# MB_Power.net
KiCad netlist of a schematic drawn in Altium Designer
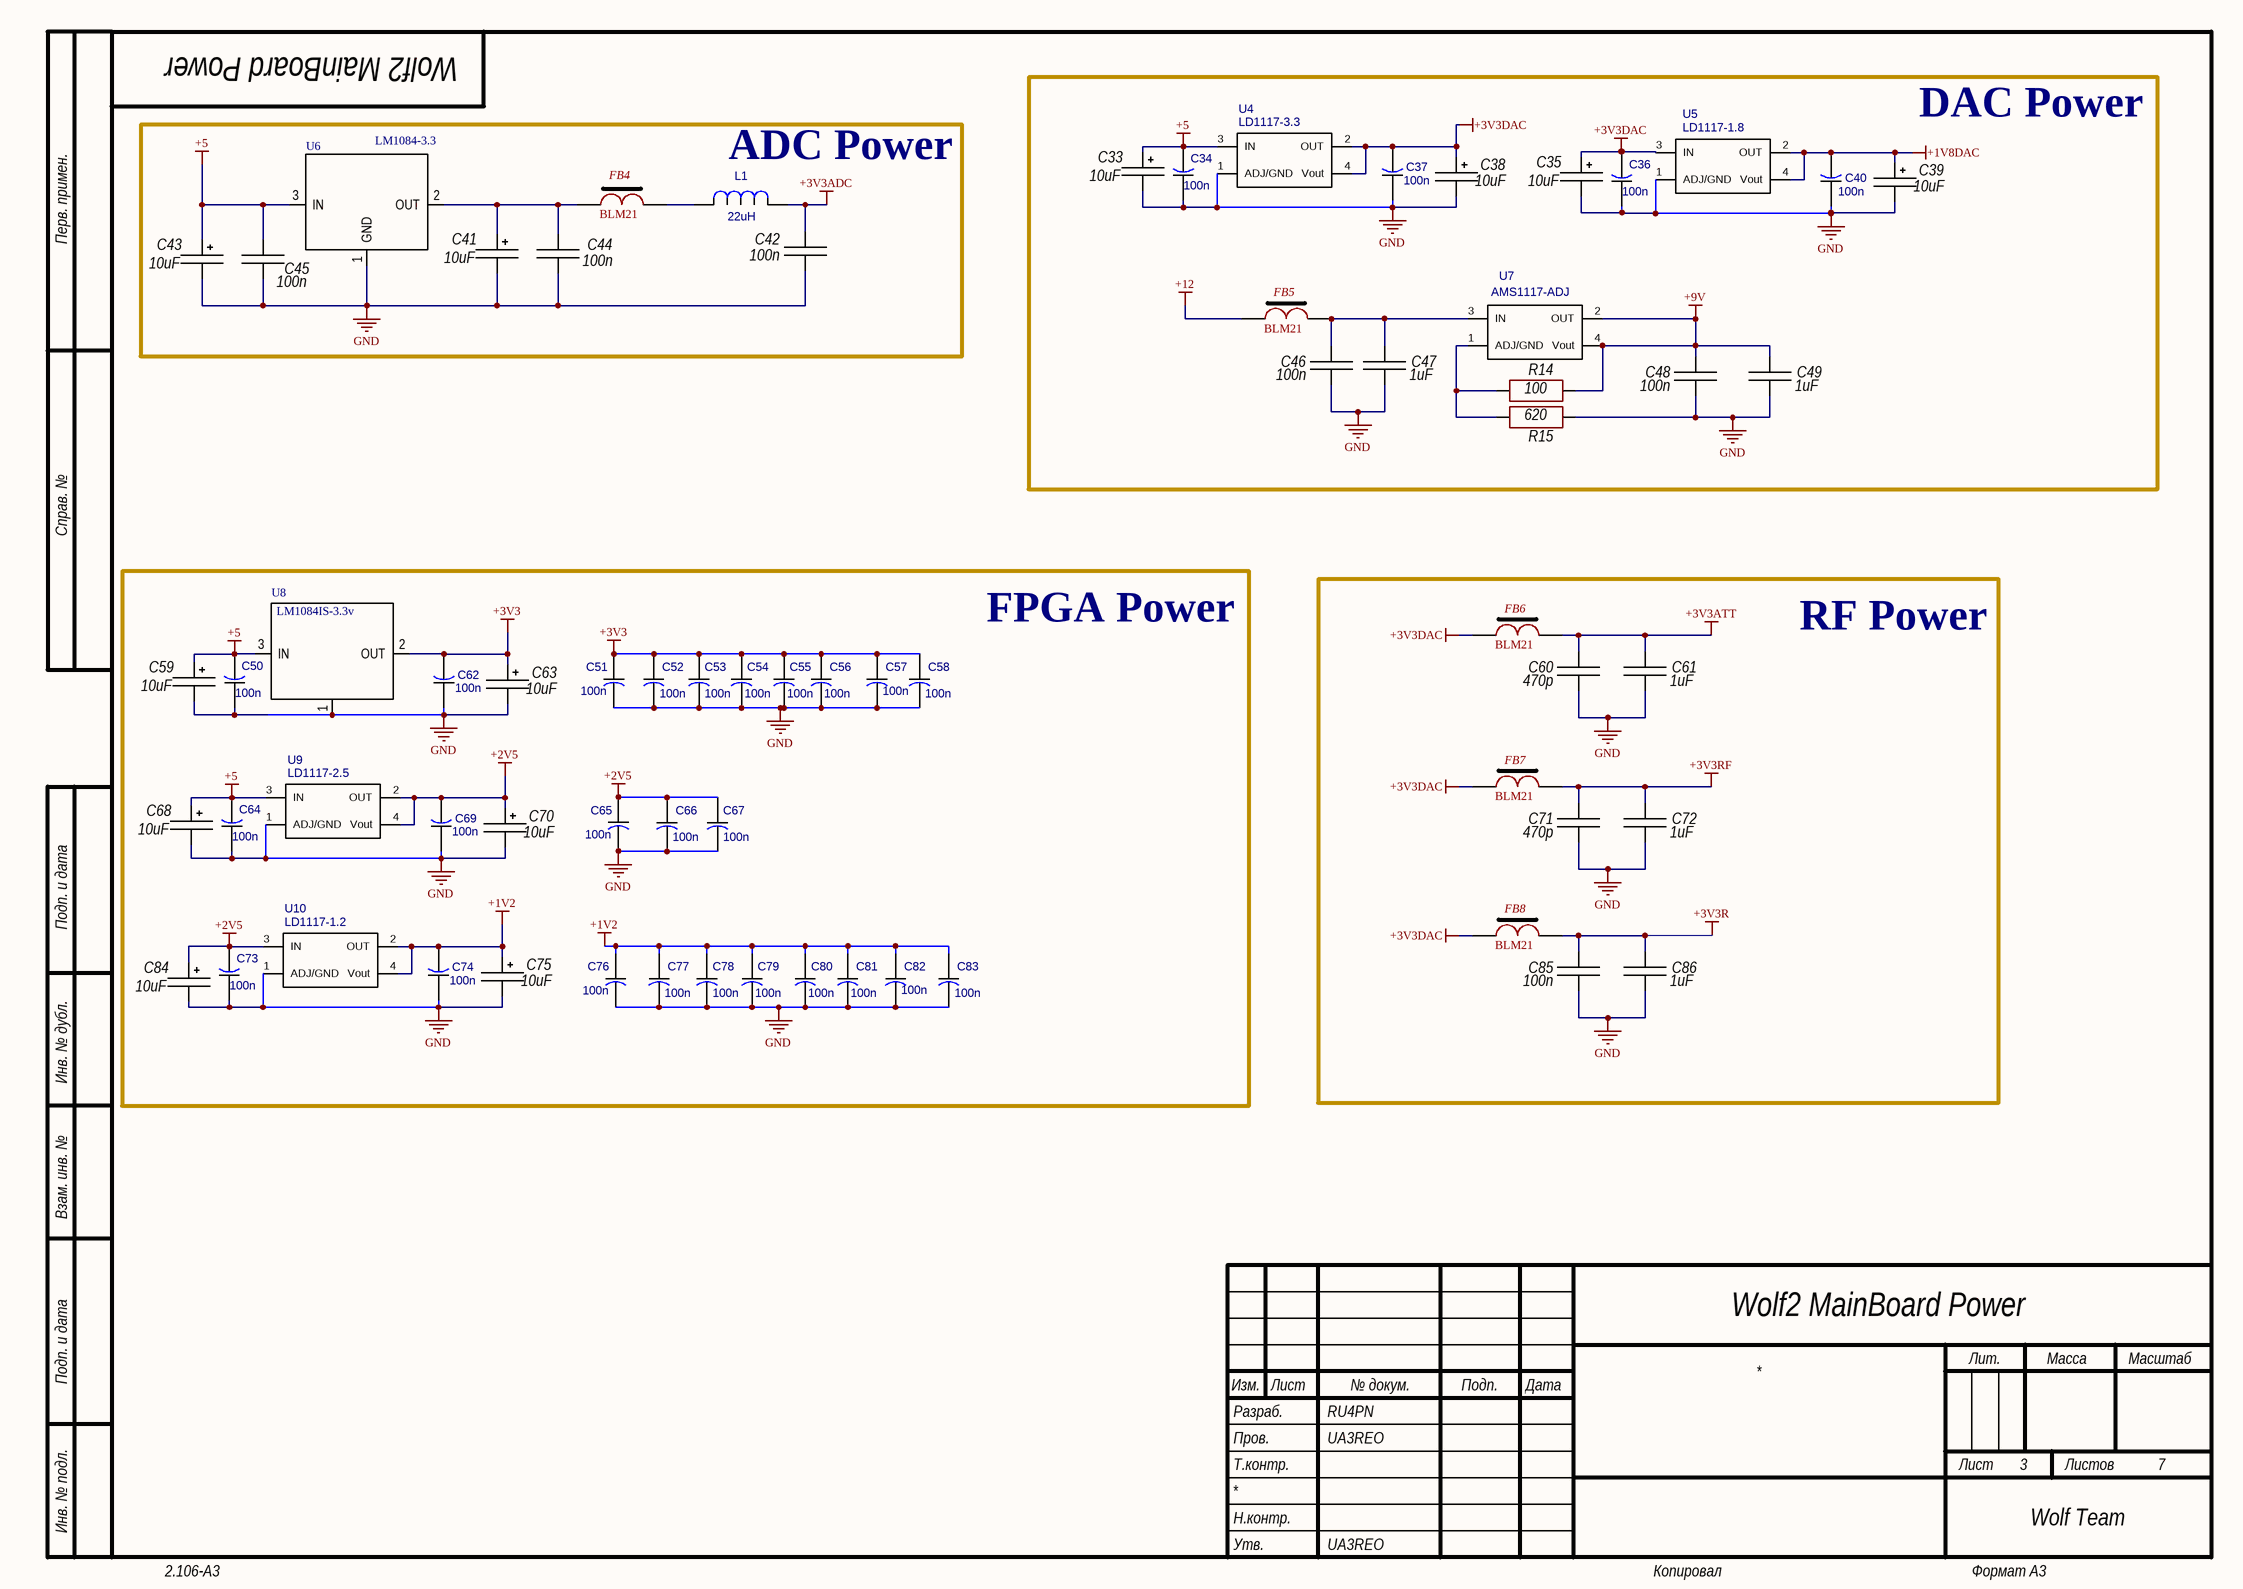
[diagram p0: MB_Power.SchDoc]

(export (version "E")
  (design (tool "Eeschema 10.0.6"))
  (components
    (comp (ref "C33")
      (value "10uF")
      (footprint "standard:TANTAL_B")
      (libsource (lib "Discrete") (part "TantalCap"))
    )
    (comp (ref "C34")
      (value "100n")
      (footprint "CAP_0805")
      (description "CAP_0805")
      (libsource (lib "*") (part "CAP_0805"))
    )
    (comp (ref "C35")
      (value "10uF")
      (footprint "standard:TANTAL_B")
      (libsource (lib "Discrete") (part "TantalCap"))
    )
    (comp (ref "C36")
      (value "100n")
      (footprint "CAP_0805")
      (description "CAP_0805")
      (libsource (lib "*") (part "CAP_0805"))
    )
    (comp (ref "C37")
      (value "100n")
      (footprint "CAP_0805")
      (description "CAP_0805")
      (libsource (lib "*") (part "CAP_0805"))
    )
    (comp (ref "C38")
      (value "10uF")
      (footprint "standard:TANTAL_B")
      (libsource (lib "Discrete") (part "TantalCap"))
    )
    (comp (ref "C39")
      (value "10uF")
      (footprint "standard:TANTAL_B")
      (libsource (lib "Discrete") (part "TantalCap"))
    )
    (comp (ref "C40")
      (value "100n")
      (footprint "CAP_0805")
      (description "CAP_0805")
      (libsource (lib "*") (part "CAP_0805"))
    )
    (comp (ref "C41")
      (value "10uF")
      (footprint "standard:TANTAL_B")
      (libsource (lib "") (part "TantalCap_1"))
    )
    (comp (ref "C42")
      (value "100n")
      (footprint "standard:CH0805C")
      (libsource (lib "Discrete") (part "Capacitor"))
    )
    (comp (ref "C43")
      (value "10uF")
      (footprint "standard:TANTAL_B")
      (libsource (lib "") (part "TantalCap_1"))
    )
    (comp (ref "C44")
      (value "100n")
      (footprint "standard:CH0805C")
      (libsource (lib "Discrete") (part "Capacitor"))
    )
    (comp (ref "C45")
      (value "100n")
      (footprint "standard:CH0805C")
      (libsource (lib "Discrete") (part "Capacitor"))
    )
    (comp (ref "C46") (value "100n") (footprint "standard:CH0805C") (libsource (lib "") (part "Capacitor_2")))
    (comp (ref "C47") (value "1uF") (footprint "standard:CH0805C") (libsource (lib "") (part "Capacitor_1")))
    (comp (ref "C48") (value "100n") (footprint "standard:CH0805C") (libsource (lib "") (part "Capacitor_1")))
    (comp (ref "C49") (value "1uF") (footprint "standard:CH0805C") (libsource (lib "") (part "Capacitor_1")))
    (comp (ref "C50")
      (value "100n")
      (footprint "CAP_0805")
      (description "CAP_0805")
      (libsource (lib "*") (part "CAP_0805"))
    )
    (comp (ref "C51")
      (value "100n")
      (footprint "CH0805C")
      (description "CAP_0805")
      (libsource (lib "*") (part "CAP_0805"))
    )
    (comp (ref "C52")
      (value "100n")
      (footprint "CH0805C")
      (description "CAP_0805")
      (libsource (lib "*") (part "CAP_0805"))
    )
    (comp (ref "C53")
      (value "100n")
      (footprint "CH0805C")
      (description "CAP_0805")
      (libsource (lib "*") (part "CAP_0805"))
    )
    (comp (ref "C54")
      (value "100n")
      (footprint "CH0805C")
      (description "CAP_0805")
      (libsource (lib "*") (part "CAP_0805"))
    )
    (comp (ref "C55")
      (value "100n")
      (footprint "CH0805C")
      (description "CAP_0805")
      (libsource (lib "*") (part "CAP_0805"))
    )
    (comp (ref "C56")
      (value "100n")
      (footprint "CH0805C")
      (description "CAP_0805")
      (libsource (lib "*") (part "CAP_0805"))
    )
    (comp (ref "C57")
      (value "100n")
      (footprint "CH0805C")
      (description "CAP_0805")
      (libsource (lib "*") (part "CAP_0805"))
    )
    (comp (ref "C58")
      (value "100n")
      (footprint "CH0805C")
      (description "CAP_0805")
      (libsource (lib "*") (part "CAP_0805"))
    )
    (comp (ref "C59")
      (value "10uF")
      (footprint "standard:TANTAL_B")
      (libsource (lib "Discrete") (part "TantalCap"))
    )
    (comp (ref "C60") (value "470p") (footprint "standard:CH0805C") (libsource (lib "") (part "Capacitor_1")))
    (comp (ref "C61") (value "1uF") (footprint "standard:CH0805C") (libsource (lib "") (part "Capacitor_1")))
    (comp (ref "C62")
      (value "100n")
      (footprint "CAP_0805")
      (description "CAP_0805")
      (libsource (lib "*") (part "CAP_0805"))
    )
    (comp (ref "C63")
      (value "10uF")
      (footprint "standard:TANTAL_B")
      (libsource (lib "Discrete") (part "TantalCap"))
    )
    (comp (ref "C64")
      (value "100n")
      (footprint "CAP_0805")
      (description "CAP_0805")
      (libsource (lib "*") (part "CAP_0805"))
    )
    (comp (ref "C65")
      (value "100n")
      (footprint "CH0805C")
      (description "CAP_0805")
      (libsource (lib "*") (part "CAP_0805"))
    )
    (comp (ref "C66")
      (value "100n")
      (footprint "CH0805C")
      (description "CAP_0805")
      (libsource (lib "*") (part "CAP_0805"))
    )
    (comp (ref "C67")
      (value "100n")
      (footprint "CH0805C")
      (description "CAP_0805")
      (libsource (lib "*") (part "CAP_0805"))
    )
    (comp (ref "C68")
      (value "10uF")
      (footprint "standard:TANTAL_B")
      (libsource (lib "Discrete") (part "TantalCap"))
    )
    (comp (ref "C69")
      (value "100n")
      (footprint "CAP_0805")
      (description "CAP_0805")
      (libsource (lib "*") (part "CAP_0805"))
    )
    (comp (ref "C70")
      (value "10uF")
      (footprint "standard:TANTAL_B")
      (libsource (lib "Discrete") (part "TantalCap"))
    )
    (comp (ref "C71") (value "470p") (footprint "standard:CH0805C") (libsource (lib "") (part "Capacitor_1")))
    (comp (ref "C72") (value "1uF") (footprint "standard:CH0805C") (libsource (lib "") (part "Capacitor_1")))
    (comp (ref "C73")
      (value "100n")
      (footprint "CAP_0805")
      (description "CAP_0805")
      (libsource (lib "*") (part "CAP_0805"))
    )
    (comp (ref "C74")
      (value "100n")
      (footprint "CAP_0805")
      (description "CAP_0805")
      (libsource (lib "*") (part "CAP_0805"))
    )
    (comp (ref "C75")
      (value "10uF")
      (footprint "standard:TANTAL_B")
      (libsource (lib "Discrete") (part "TantalCap"))
    )
    (comp (ref "C76")
      (value "100n")
      (footprint "CH0805C")
      (description "CAP_0805")
      (libsource (lib "*") (part "CAP_0805"))
    )
    (comp (ref "C77")
      (value "100n")
      (footprint "CH0805C")
      (description "CAP_0805")
      (libsource (lib "*") (part "CAP_0805"))
    )
    (comp (ref "C78")
      (value "100n")
      (footprint "CH0805C")
      (description "CAP_0805")
      (libsource (lib "*") (part "CAP_0805"))
    )
    (comp (ref "C79")
      (value "100n")
      (footprint "CH0805C")
      (description "CAP_0805")
      (libsource (lib "*") (part "CAP_0805"))
    )
    (comp (ref "C80")
      (value "100n")
      (footprint "CH0805C")
      (description "CAP_0805")
      (libsource (lib "*") (part "CAP_0805"))
    )
    (comp (ref "C81")
      (value "100n")
      (footprint "CH0805C")
      (description "CAP_0805")
      (libsource (lib "*") (part "CAP_0805"))
    )
    (comp (ref "C82")
      (value "100n")
      (footprint "CH0805C")
      (description "CAP_0805")
      (libsource (lib "*") (part "CAP_0805"))
    )
    (comp (ref "C83")
      (value "100n")
      (footprint "CH0805C")
      (description "CAP_0805")
      (libsource (lib "*") (part "CAP_0805"))
    )
    (comp (ref "C84")
      (value "10uF")
      (footprint "standard:TANTAL_B")
      (libsource (lib "Discrete") (part "TantalCap"))
    )
    (comp (ref "C85") (value "100n") (footprint "standard:CH0805C") (libsource (lib "") (part "Capacitor_1")))
    (comp (ref "C86") (value "1uF") (footprint "standard:CH0805C") (libsource (lib "") (part "Capacitor_1")))
    (comp (ref "FB4") (value "BLM21") (footprint "CH0805L") (libsource (lib "Discrete") (part "FB-1")))
    (comp (ref "FB5") (value "BLM21") (footprint "CH0805L") (libsource (lib "Discrete") (part "FB-1")))
    (comp (ref "FB6") (value "BLM21") (footprint "CH0805L") (libsource (lib "Discrete") (part "FB-1")))
    (comp (ref "FB7") (value "BLM21") (footprint "CH0805L") (libsource (lib "Discrete") (part "FB-1")))
    (comp (ref "FB8") (value "BLM21") (footprint "CH0805L") (libsource (lib "Discrete") (part "FB-1")))
    (comp (ref "L1")
      (value "22uH")
      (footprint "IND_7x7")
      (description "IND_1206")
      (libsource (lib "*") (part "IND_1206"))
    )
    (comp (ref "R14")
      (value "100")
      (footprint "standard:CH0805R")
      (libsource (lib "Discrete") (part "Resistor"))
    )
    (comp (ref "R15")
      (value "620")
      (footprint "standard:CH0805R")
      (libsource (lib "Discrete") (part "Resistor"))
    )
    (comp (ref "U4")
      (value "LD1117-3.3")
      (footprint "LT1117CST-3.3_2")
      (description "LT1117CST-3.3")
      (fields (field (name "Comment") "1117-3.3"))
      (libsource (lib "*") (part "LT1117CST-3.3"))
    )
    (comp (ref "U5")
      (value "LD1117-1.8")
      (footprint "LT1117CST-3.3")
      (description "LT1117CST-1.8")
      (fields (field (name "Comment") "1117-1.8"))
      (libsource (lib "*") (part "LT1117CST-3.3"))
    )
    (comp (ref "U6")
      (value "LM1084-3.3")
      (footprint "LM1084-3.3")
      (libsource (lib "Power Supplies") (part "LM1084"))
    )
    (comp (ref "U7")
      (value "AMS1117-ADJ")
      (footprint "LT1117CST-3.3")
      (description "LT1117CST-ADJ")
      (fields (field (name "Comment") "1117-ADJ"))
      (libsource (lib "*") (part "LT1117CST-3.3"))
    )
    (comp (ref "U8")
      (value "LM1084IS-3.3v")
      (footprint "LM1084-3.3")
      (libsource (lib "Power Supplies") (part "LM1084"))
    )
    (comp (ref "U9")
      (value "LD1117-2.5")
      (footprint "LT1117CST-3.3_2")
      (description "LT1117CST-2.5")
      (fields (field (name "Comment") "1117-2.5"))
      (libsource (lib "*") (part "LT1117CST-3.3"))
    )
    (comp (ref "U10")
      (value "LD1117-1.2")
      (footprint "LT1117CST-3.3_2")
      (description "LT1117CST-1.2")
      (fields (field (name "Comment") "1117-1.2"))
      (libsource (lib "*") (part "LT1117CST-3.3"))
    )
  )
  (nets
    (net (code "1") (name "+1V2") (class "Default")
      (node (ref "C74") (pin "2") (pinfunction "2_2") (pintype "passive"))
      (node (ref "C75") (pin "1") (pinfunction "1_1") (pintype "power_in"))
      (node (ref "C76") (pin "1") (pinfunction "1_1") (pintype "passive"))
      (node (ref "C77") (pin "1") (pinfunction "1_1") (pintype "passive"))
      (node (ref "C78") (pin "1") (pinfunction "1_1") (pintype "passive"))
      (node (ref "C79") (pin "1") (pinfunction "1_1") (pintype "passive"))
      (node (ref "C80") (pin "1") (pinfunction "1_1") (pintype "passive"))
      (node (ref "C81") (pin "1") (pinfunction "1_1") (pintype "passive"))
      (node (ref "C82") (pin "1") (pinfunction "1_1") (pintype "passive"))
      (node (ref "C83") (pin "1") (pinfunction "1_1") (pintype "passive"))
      (node (ref "U10") (pin "2") (pinfunction "OUT_2") (pintype "passive"))
      (node (ref "U10") (pin "4") (pinfunction "Vout_4") (pintype "passive"))
    )
    (net (code "2") (name "+1V8DAC") (class "Default")
      (node (ref "C39") (pin "1") (pinfunction "1_1") (pintype "power_in"))
      (node (ref "C40") (pin "2") (pinfunction "2_2") (pintype "passive"))
      (node (ref "U5") (pin "2") (pinfunction "OUT_2") (pintype "passive"))
      (node (ref "U5") (pin "4") (pinfunction "Vout_4") (pintype "passive"))
    )
    (net (code "3") (name "+2V5") (class "Default")
      (node (ref "C65") (pin "1") (pinfunction "1_1") (pintype "passive"))
      (node (ref "C66") (pin "1") (pinfunction "1_1") (pintype "passive"))
      (node (ref "C67") (pin "1") (pinfunction "1_1") (pintype "passive"))
      (node (ref "C69") (pin "2") (pinfunction "2_2") (pintype "passive"))
      (node (ref "C70") (pin "1") (pinfunction "1_1") (pintype "power_in"))
      (node (ref "C73") (pin "2") (pinfunction "2_2") (pintype "passive"))
      (node (ref "C84") (pin "1") (pinfunction "1_1") (pintype "power_in"))
      (node (ref "U10") (pin "3") (pinfunction "IN_3") (pintype "passive"))
      (node (ref "U9") (pin "2") (pinfunction "OUT_2") (pintype "passive"))
      (node (ref "U9") (pin "4") (pinfunction "Vout_4") (pintype "passive"))
    )
    (net (code "4") (name "+3V3") (class "Default")
      (node (ref "C51") (pin "1") (pinfunction "1_1") (pintype "passive"))
      (node (ref "C52") (pin "1") (pinfunction "1_1") (pintype "passive"))
      (node (ref "C53") (pin "1") (pinfunction "1_1") (pintype "passive"))
      (node (ref "C54") (pin "1") (pinfunction "1_1") (pintype "passive"))
      (node (ref "C55") (pin "1") (pinfunction "1_1") (pintype "passive"))
      (node (ref "C56") (pin "1") (pinfunction "1_1") (pintype "passive"))
      (node (ref "C57") (pin "1") (pinfunction "1_1") (pintype "passive"))
      (node (ref "C58") (pin "1") (pinfunction "1_1") (pintype "passive"))
      (node (ref "C62") (pin "2") (pinfunction "2_2") (pintype "passive"))
      (node (ref "C63") (pin "1") (pinfunction "1_1") (pintype "power_in"))
      (node (ref "U8") (pin "2") (pinfunction "OUT_2") (pintype "passive"))
    )
    (net (code "5") (name "+3V3ADC") (class "Default")
      (node (ref "C42") (pin "1") (pinfunction "1_1") (pintype "power_in"))
      (node (ref "L1") (pin "2") (pinfunction "2_2") (pintype "passive"))
    )
    (net (code "6") (name "+3V3ATT") (class "Default")
      (node (ref "C60") (pin "1") (pinfunction "1_1") (pintype "power_in"))
      (node (ref "C61") (pin "1") (pinfunction "1_1") (pintype "power_in"))
      (node (ref "FB6") (pin "1") (pinfunction "1_1") (pintype "passive"))
    )
    (net (code "7") (name "+3V3DAC") (class "Default")
      (node (ref "C35") (pin "1") (pinfunction "1_1") (pintype "power_in"))
      (node (ref "C36") (pin "2") (pinfunction "2_2") (pintype "passive"))
      (node (ref "C37") (pin "2") (pinfunction "2_2") (pintype "passive"))
      (node (ref "C38") (pin "1") (pinfunction "1_1") (pintype "power_in"))
      (node (ref "FB6") (pin "2") (pinfunction "2_2") (pintype "passive"))
      (node (ref "FB7") (pin "2") (pinfunction "2_2") (pintype "passive"))
      (node (ref "FB8") (pin "2") (pinfunction "2_2") (pintype "passive"))
      (node (ref "U4") (pin "2") (pinfunction "OUT_2") (pintype "passive"))
      (node (ref "U4") (pin "4") (pinfunction "Vout_4") (pintype "passive"))
      (node (ref "U5") (pin "3") (pinfunction "IN_3") (pintype "passive"))
    )
    (net (code "8") (name "+3V3R") (class "Default")
      (node (ref "C85") (pin "1") (pinfunction "1_1") (pintype "power_in"))
      (node (ref "C86") (pin "1") (pinfunction "1_1") (pintype "power_in"))
      (node (ref "FB8") (pin "1") (pinfunction "1_1") (pintype "passive"))
    )
    (net (code "9") (name "+3V3RF") (class "Default")
      (node (ref "C71") (pin "1") (pinfunction "1_1") (pintype "power_in"))
      (node (ref "C72") (pin "1") (pinfunction "1_1") (pintype "power_in"))
      (node (ref "FB7") (pin "1") (pinfunction "1_1") (pintype "passive"))
    )
    (net (code "10") (name "+5") (class "Default")
      (node (ref "C33") (pin "1") (pinfunction "1_1") (pintype "power_in"))
      (node (ref "C34") (pin "2") (pinfunction "2_2") (pintype "passive"))
      (node (ref "C43") (pin "1") (pinfunction "1_1") (pintype "power_in"))
      (node (ref "C45") (pin "1") (pinfunction "1_1") (pintype "power_in"))
      (node (ref "C50") (pin "2") (pinfunction "2_2") (pintype "passive"))
      (node (ref "C59") (pin "1") (pinfunction "1_1") (pintype "power_in"))
      (node (ref "C64") (pin "2") (pinfunction "2_2") (pintype "passive"))
      (node (ref "C68") (pin "1") (pinfunction "1_1") (pintype "power_in"))
      (node (ref "U4") (pin "3") (pinfunction "IN_3") (pintype "passive"))
      (node (ref "U6") (pin "3") (pinfunction "IN_3") (pintype "passive"))
      (node (ref "U8") (pin "3") (pinfunction "IN_3") (pintype "passive"))
      (node (ref "U9") (pin "3") (pinfunction "IN_3") (pintype "passive"))
    )
    (net (code "11") (name "+9V") (class "Default")
      (node (ref "C48") (pin "1") (pinfunction "1_1") (pintype "power_in"))
      (node (ref "C49") (pin "1") (pinfunction "1_1") (pintype "power_in"))
      (node (ref "R14") (pin "1") (pinfunction "1_1") (pintype "passive"))
      (node (ref "U7") (pin "2") (pinfunction "OUT_2") (pintype "passive"))
      (node (ref "U7") (pin "4") (pinfunction "Vout_4") (pintype "passive"))
    )
    (net (code "12") (name "+12") (class "Default")
      (node (ref "FB5") (pin "2") (pinfunction "2_2") (pintype "passive"))
    )
    (net (code "13") (name "GND") (class "Default")
      (node (ref "C33") (pin "2") (pinfunction "2_2") (pintype "power_in"))
      (node (ref "C34") (pin "1") (pinfunction "1_1") (pintype "passive"))
      (node (ref "C35") (pin "2") (pinfunction "2_2") (pintype "power_in"))
      (node (ref "C36") (pin "1") (pinfunction "1_1") (pintype "passive"))
      (node (ref "C37") (pin "1") (pinfunction "1_1") (pintype "passive"))
      (node (ref "C38") (pin "2") (pinfunction "2_2") (pintype "power_in"))
      (node (ref "C39") (pin "2") (pinfunction "2_2") (pintype "power_in"))
      (node (ref "C40") (pin "1") (pinfunction "1_1") (pintype "passive"))
      (node (ref "C41") (pin "2") (pinfunction "2_2") (pintype "power_in"))
      (node (ref "C42") (pin "2") (pinfunction "2_2") (pintype "power_in"))
      (node (ref "C43") (pin "2") (pinfunction "2_2") (pintype "power_in"))
      (node (ref "C44") (pin "2") (pinfunction "2_2") (pintype "power_in"))
      (node (ref "C45") (pin "2") (pinfunction "2_2") (pintype "power_in"))
      (node (ref "C46") (pin "2") (pinfunction "2_2") (pintype "power_in"))
      (node (ref "C47") (pin "2") (pinfunction "2_2") (pintype "power_in"))
      (node (ref "C48") (pin "2") (pinfunction "2_2") (pintype "power_in"))
      (node (ref "C49") (pin "2") (pinfunction "2_2") (pintype "power_in"))
      (node (ref "C50") (pin "1") (pinfunction "1_1") (pintype "passive"))
      (node (ref "C51") (pin "2") (pinfunction "2_2") (pintype "passive"))
      (node (ref "C52") (pin "2") (pinfunction "2_2") (pintype "passive"))
      (node (ref "C53") (pin "2") (pinfunction "2_2") (pintype "passive"))
      (node (ref "C54") (pin "2") (pinfunction "2_2") (pintype "passive"))
      (node (ref "C55") (pin "2") (pinfunction "2_2") (pintype "passive"))
      (node (ref "C56") (pin "2") (pinfunction "2_2") (pintype "passive"))
      (node (ref "C57") (pin "2") (pinfunction "2_2") (pintype "passive"))
      (node (ref "C58") (pin "2") (pinfunction "2_2") (pintype "passive"))
      (node (ref "C59") (pin "2") (pinfunction "2_2") (pintype "power_in"))
      (node (ref "C60") (pin "2") (pinfunction "2_2") (pintype "power_in"))
      (node (ref "C61") (pin "2") (pinfunction "2_2") (pintype "power_in"))
      (node (ref "C62") (pin "1") (pinfunction "1_1") (pintype "passive"))
      (node (ref "C63") (pin "2") (pinfunction "2_2") (pintype "power_in"))
      (node (ref "C64") (pin "1") (pinfunction "1_1") (pintype "passive"))
      (node (ref "C65") (pin "2") (pinfunction "2_2") (pintype "passive"))
      (node (ref "C66") (pin "2") (pinfunction "2_2") (pintype "passive"))
      (node (ref "C67") (pin "2") (pinfunction "2_2") (pintype "passive"))
      (node (ref "C68") (pin "2") (pinfunction "2_2") (pintype "power_in"))
      (node (ref "C69") (pin "1") (pinfunction "1_1") (pintype "passive"))
      (node (ref "C70") (pin "2") (pinfunction "2_2") (pintype "power_in"))
      (node (ref "C71") (pin "2") (pinfunction "2_2") (pintype "power_in"))
      (node (ref "C72") (pin "2") (pinfunction "2_2") (pintype "power_in"))
      (node (ref "C73") (pin "1") (pinfunction "1_1") (pintype "passive"))
      (node (ref "C74") (pin "1") (pinfunction "1_1") (pintype "passive"))
      (node (ref "C75") (pin "2") (pinfunction "2_2") (pintype "power_in"))
      (node (ref "C76") (pin "2") (pinfunction "2_2") (pintype "passive"))
      (node (ref "C77") (pin "2") (pinfunction "2_2") (pintype "passive"))
      (node (ref "C78") (pin "2") (pinfunction "2_2") (pintype "passive"))
      (node (ref "C79") (pin "2") (pinfunction "2_2") (pintype "passive"))
      (node (ref "C80") (pin "2") (pinfunction "2_2") (pintype "passive"))
      (node (ref "C81") (pin "2") (pinfunction "2_2") (pintype "passive"))
      (node (ref "C82") (pin "2") (pinfunction "2_2") (pintype "passive"))
      (node (ref "C83") (pin "2") (pinfunction "2_2") (pintype "passive"))
      (node (ref "C84") (pin "2") (pinfunction "2_2") (pintype "power_in"))
      (node (ref "C85") (pin "2") (pinfunction "2_2") (pintype "power_in"))
      (node (ref "C86") (pin "2") (pinfunction "2_2") (pintype "power_in"))
      (node (ref "R15") (pin "1") (pinfunction "1_1") (pintype "passive"))
      (node (ref "U10") (pin "1") (pinfunction "ADJ/GND_1") (pintype "passive"))
      (node (ref "U4") (pin "1") (pinfunction "ADJ/GND_1") (pintype "passive"))
      (node (ref "U5") (pin "1") (pinfunction "ADJ/GND_1") (pintype "passive"))
      (node (ref "U6") (pin "1") (pintype "passive"))
      (node (ref "U8") (pin "1") (pintype "passive"))
      (node (ref "U9") (pin "1") (pinfunction "ADJ/GND_1") (pintype "passive"))
    )
    (net (code "14") (name "Net-(FB4-Pad1)") (class "Default")
      (node (ref "FB4") (pin "1") (pinfunction "1_1") (pintype "passive"))
      (node (ref "L1") (pin "1") (pinfunction "1_1") (pintype "passive"))
    )
    (net (code "15") (name "Net-(U6-OUT)") (class "Default")
      (node (ref "C41") (pin "1") (pinfunction "1_1") (pintype "power_in"))
      (node (ref "C44") (pin "1") (pinfunction "1_1") (pintype "power_in"))
      (node (ref "FB4") (pin "2") (pinfunction "2_2") (pintype "passive"))
      (node (ref "U6") (pin "2") (pinfunction "OUT_2") (pintype "passive"))
    )
    (net (code "16") (name "Net-(U7-ADJ{slash}GND)") (class "Default")
      (node (ref "R14") (pin "2") (pinfunction "2_2") (pintype "passive"))
      (node (ref "R15") (pin "2") (pinfunction "2_2") (pintype "passive"))
      (node (ref "U7") (pin "1") (pinfunction "ADJ/GND_1") (pintype "passive"))
    )
    (net (code "17") (name "Net-(U7-IN)") (class "Default")
      (node (ref "C46") (pin "1") (pinfunction "1_1") (pintype "power_in"))
      (node (ref "C47") (pin "1") (pinfunction "1_1") (pintype "power_in"))
      (node (ref "FB5") (pin "1") (pinfunction "1_1") (pintype "passive"))
      (node (ref "U7") (pin "3") (pinfunction "IN_3") (pintype "passive"))
    )
  )
)
